# Main.net
KiCad netlist of a schematic drawn in Altium Designer
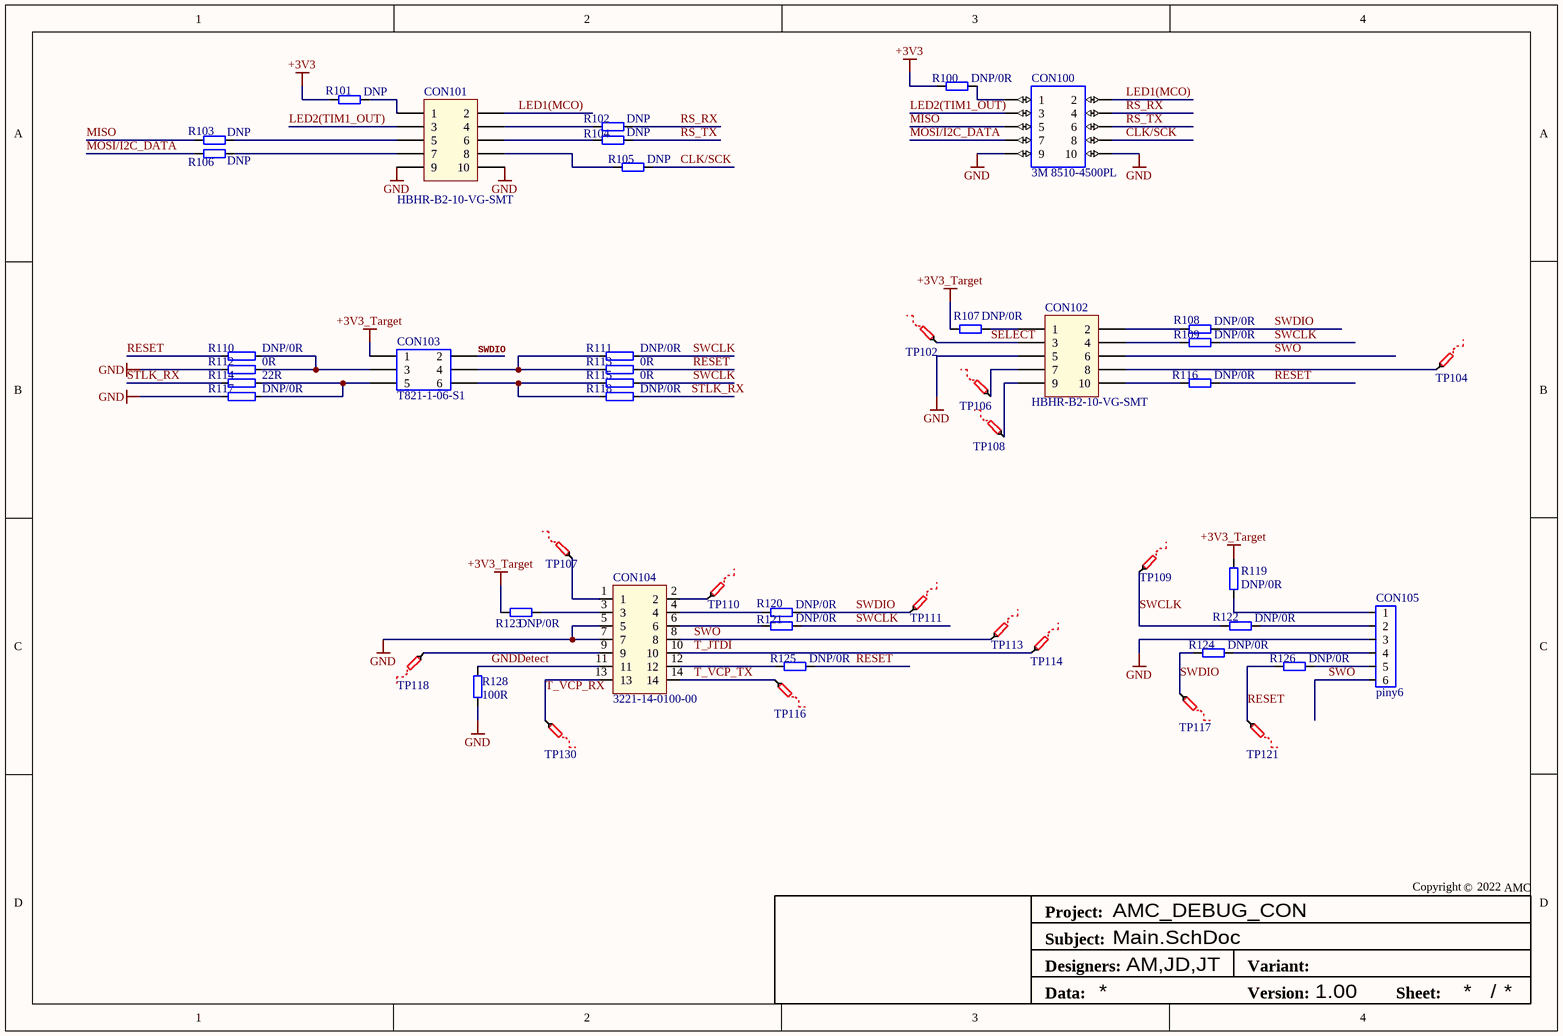
[diagram p0: Main.SchDoc]

(export (version "E")
  (design (tool "Eeschema 10.0.6"))
  (components
    (comp (ref "CON100")
      (value "3M 8510-4500PL")
      (footprint "PINY2X5 zenskie")
      (description "Gniazdo; IDC; żeńskie; PIN: 10; proste; THT; złocony; 3A; 2,54mm")
      (libsource (lib "ECS_AMC_all_2016") (part "piny_2x5 zenskie Petroster"))
    )
    (comp (ref "CON101")
      (value "HBHR-B2-10-VG-SMT")
      (footprint "piny_1k27_2x5_smd_IDC")
      (description "AMC Debug connector\r\nIDC 2x5 pitch 1.27")
      (libsource (lib "ECS_AMC_all_2016") (part "AMC_Debug"))
    )
    (comp (ref "CON102")
      (value "HBHR-B2-10-VG-SMT")
      (footprint "piny_1k27_2x5_smd_IDC")
      (description "AMC Debug connector\r\nIDC 2x5 pitch 1.27")
      (libsource (lib "ECS_AMC_all_2016") (part "AMC_Debug"))
    )
    (comp (ref "CON103")
      (value "T821-1-06-S1")
      (footprint "IDC_2X3_2.54MM")
      (libsource (lib "ECS_AMC_all_2016") (part "piny_2x3"))
    )
    (comp (ref "CON104")
      (value "3221-14-0100-00")
      (footprint "PINY_2X7_1.27_THT")
      (description "CONN HEADER VERT 14POS 1.27MM")
      (libsource (lib "ECS_AMC_all_2016") (part "3221-14-0100-00"))
    )
    (comp (ref "CON105")
      (value "piny6")
      (footprint "piny1x6")
      (libsource (lib "ECS_AMC_all_2016") (part "piny6"))
    )
    (comp (ref "R100") (value "DNP/0R") (footprint "0805") (libsource (lib "ECS_all_2014") (part "rez_3k")))
    (comp (ref "R101") (value "DNP") (footprint "0805") (libsource (lib "ECS_all_2014") (part "rez_3k")))
    (comp (ref "R102") (value "DNP") (footprint "0805") (libsource (lib "ECS_all_2014") (part "rez_3k")))
    (comp (ref "R103") (value "DNP") (footprint "0805") (libsource (lib "ECS_all_2014") (part "rez_3k")))
    (comp (ref "R104") (value "DNP") (footprint "0805") (libsource (lib "ECS_all_2014") (part "rez_3k")))
    (comp (ref "R105") (value "DNP") (footprint "0805") (libsource (lib "ECS_all_2014") (part "rez_3k")))
    (comp (ref "R106") (value "DNP") (footprint "0805") (libsource (lib "ECS_all_2014") (part "rez_3k")))
    (comp (ref "R107") (value "DNP/0R") (footprint "0805") (libsource (lib "ECS_all_2014") (part "rez_3k")))
    (comp (ref "R108") (value "DNP/0R") (footprint "0805") (libsource (lib "ECS_all_2014") (part "rez_3k")))
    (comp (ref "R109") (value "DNP/0R") (footprint "0805") (libsource (lib "ECS_all_2014") (part "rez_3k")))
    (comp (ref "R110") (value "DNP/0R") (footprint "0805") (libsource (lib "ECS_AMC_all_2016") (part "RES")))
    (comp (ref "R111") (value "DNP/0R") (footprint "0805") (libsource (lib "ECS_AMC_all_2016") (part "RES")))
    (comp (ref "R112") (value "0R") (footprint "0805") (libsource (lib "ECS_AMC_all_2016") (part "RES")))
    (comp (ref "R113") (value "0R") (footprint "0805") (libsource (lib "ECS_AMC_all_2016") (part "RES")))
    (comp (ref "R114") (value "22R") (footprint "0805") (libsource (lib "ECS_AMC_all_2016") (part "RES")))
    (comp (ref "R115") (value "0R") (footprint "0805") (libsource (lib "ECS_AMC_all_2016") (part "RES")))
    (comp (ref "R116") (value "DNP/0R") (footprint "0805") (libsource (lib "ECS_all_2014") (part "rez_3k")))
    (comp (ref "R117") (value "DNP/0R") (footprint "0805") (libsource (lib "ECS_AMC_all_2016") (part "RES")))
    (comp (ref "R118") (value "DNP/0R") (footprint "0805") (libsource (lib "ECS_AMC_all_2016") (part "RES")))
    (comp (ref "R119") (value "DNP/0R") (footprint "0805") (libsource (lib "") (part "rez_3k_1")))
    (comp (ref "R120") (value "DNP/0R") (footprint "0805") (libsource (lib "ECS_all_2014") (part "rez_3k")))
    (comp (ref "R121") (value "DNP/0R") (footprint "0805") (libsource (lib "ECS_all_2014") (part "rez_3k")))
    (comp (ref "R122") (value "DNP/0R") (footprint "0805") (libsource (lib "ECS_all_2014") (part "rez_3k")))
    (comp (ref "R123") (value "DNP/0R") (footprint "0805") (libsource (lib "") (part "rez_3k_2")))
    (comp (ref "R124") (value "DNP/0R") (footprint "0805") (libsource (lib "ECS_all_2014") (part "rez_3k")))
    (comp (ref "R125") (value "DNP/0R") (footprint "0805") (libsource (lib "ECS_all_2014") (part "rez_3k")))
    (comp (ref "R126") (value "DNP/0R") (footprint "0805") (libsource (lib "ECS_all_2014") (part "rez_3k")))
    (comp (ref "R128") (value "100R") (footprint "0805") (libsource (lib "") (part "rez_3k_1")))
    (comp (ref "TP102")
      (value "testpoint")
      (footprint "testpoint_50mils_octagonal")
      (description "Testpoint")
      (libsource (lib "ECS_AMC_all_2016") (part "testpoint"))
    )
    (comp (ref "TP104")
      (value "testpoint")
      (footprint "testpoint_50mils_octagonal")
      (description "Testpoint")
      (libsource (lib "ECS_AMC_all_2016") (part "testpoint"))
    )
    (comp (ref "TP106")
      (value "testpoint")
      (footprint "testpoint_50mils_octagonal")
      (description "Testpoint")
      (libsource (lib "ECS_AMC_all_2016") (part "testpoint"))
    )
    (comp (ref "TP107")
      (value "testpoint")
      (footprint "testpoint_50mils_octagonal")
      (description "Testpoint")
      (libsource (lib "ECS_AMC_all_2016") (part "testpoint"))
    )
    (comp (ref "TP108")
      (value "testpoint")
      (footprint "testpoint_50mils_octagonal")
      (description "Testpoint")
      (libsource (lib "ECS_AMC_all_2016") (part "testpoint"))
    )
    (comp (ref "TP109")
      (value "testpoint")
      (footprint "testpoint_50mils_octagonal")
      (description "Testpoint")
      (libsource (lib "ECS_AMC_all_2016") (part "testpoint"))
    )
    (comp (ref "TP110")
      (value "testpoint")
      (footprint "testpoint_50mils_octagonal")
      (description "Testpoint")
      (libsource (lib "ECS_AMC_all_2016") (part "testpoint"))
    )
    (comp (ref "TP111")
      (value "testpoint")
      (footprint "testpoint_50mils_octagonal")
      (description "Testpoint")
      (libsource (lib "ECS_AMC_all_2016") (part "testpoint"))
    )
    (comp (ref "TP113")
      (value "testpoint")
      (footprint "testpoint_50mils_octagonal")
      (description "Testpoint")
      (libsource (lib "ECS_AMC_all_2016") (part "testpoint"))
    )
    (comp (ref "TP114")
      (value "testpoint")
      (footprint "testpoint_50mils_octagonal")
      (description "Testpoint")
      (libsource (lib "ECS_AMC_all_2016") (part "testpoint"))
    )
    (comp (ref "TP116")
      (value "testpoint")
      (footprint "testpoint_50mils_octagonal")
      (description "Testpoint")
      (libsource (lib "ECS_AMC_all_2016") (part "testpoint"))
    )
    (comp (ref "TP117")
      (value "testpoint")
      (footprint "testpoint_50mils_octagonal")
      (description "Testpoint")
      (libsource (lib "ECS_AMC_all_2016") (part "testpoint"))
    )
    (comp (ref "TP118")
      (value "testpoint")
      (footprint "testpoint_50mils_octagonal")
      (description "Testpoint")
      (libsource (lib "ECS_AMC_all_2016") (part "testpoint"))
    )
    (comp (ref "TP121")
      (value "testpoint")
      (footprint "testpoint_50mils_octagonal")
      (description "Testpoint")
      (libsource (lib "ECS_AMC_all_2016") (part "testpoint"))
    )
    (comp (ref "TP130")
      (value "testpoint")
      (footprint "testpoint_50mils_octagonal")
      (description "Testpoint")
      (libsource (lib "ECS_AMC_all_2016") (part "testpoint"))
    )
  )
  (nets
    (net (code "1") (name "+3V3") (class "Default")
      (node (ref "R100") (pin "1") (pinfunction "1_1") (pintype "passive"))
      (node (ref "R101") (pin "1") (pinfunction "1_1") (pintype "passive"))
    )
    (net (code "2") (name "+3V3_Target") (class "Default")
      (node (ref "CON103") (pin "1") (pinfunction "1_1") (pintype "passive"))
      (node (ref "R107") (pin "1") (pinfunction "1_1") (pintype "passive"))
      (node (ref "R119") (pin "2") (pinfunction "2_2") (pintype "passive"))
      (node (ref "R123") (pin "2") (pinfunction "2_2") (pintype "passive"))
    )
    (net (code "3") (name "/CLK{slash}SCK") (class "Default")
      (node (ref "CON100") (pin "8") (pinfunction "8_8") (pintype "bidirectional"))
      (node (ref "R105") (pin "2") (pinfunction "2_2") (pintype "passive"))
    )
    (net (code "4") (name "/GNDDetect") (class "Default")
      (node (ref "CON104") (pin "11") (pinfunction "11_11") (pintype "passive"))
      (node (ref "R128") (pin "2") (pinfunction "2_2") (pintype "passive"))
    )
    (net (code "5") (name "/LED1(MCO)") (class "Default")
      (node (ref "CON100") (pin "2") (pinfunction "2_2") (pintype "bidirectional"))
      (node (ref "CON101") (pin "2") (pinfunction "2_2") (pintype "passive"))
    )
    (net (code "6") (name "/LED2(TIM1_OUT)") (class "Default")
      (node (ref "CON100") (pin "3") (pinfunction "3_3") (pintype "bidirectional"))
      (node (ref "CON101") (pin "3") (pinfunction "3_3") (pintype "passive"))
    )
    (net (code "7") (name "/MISO") (class "Default")
      (node (ref "CON100") (pin "5") (pinfunction "5_5") (pintype "bidirectional"))
      (node (ref "R103") (pin "1") (pinfunction "1_1") (pintype "passive"))
    )
    (net (code "8") (name "/MOSI{slash}I2C_DATA") (class "Default")
      (node (ref "CON100") (pin "7") (pinfunction "7_7") (pintype "bidirectional"))
      (node (ref "R106") (pin "1") (pinfunction "1_1") (pintype "passive"))
    )
    (net (code "9") (name "/RESET") (class "Default")
      (node (ref "R110") (pin "2") (pinfunction "2_2") (pintype "passive"))
      (node (ref "R113") (pin "1") (pinfunction "1_1") (pintype "passive"))
      (node (ref "R116") (pin "2") (pinfunction "2_2") (pintype "passive"))
      (node (ref "R125") (pin "2") (pinfunction "2_2") (pintype "passive"))
      (node (ref "R126") (pin "1") (pinfunction "1_1") (pintype "passive"))
      (node (ref "TP121") (pin "1") (pinfunction "1_1") (pintype "passive"))
    )
    (net (code "10") (name "/RS_RX") (class "Default")
      (node (ref "CON100") (pin "4") (pinfunction "4_4") (pintype "bidirectional"))
      (node (ref "R102") (pin "2") (pinfunction "2_2") (pintype "passive"))
    )
    (net (code "11") (name "/RS_TX") (class "Default")
      (node (ref "CON100") (pin "6") (pinfunction "6_6") (pintype "bidirectional"))
      (node (ref "R104") (pin "2") (pinfunction "2_2") (pintype "passive"))
    )
    (net (code "12") (name "/SELECT") (class "Default")
      (node (ref "CON102") (pin "3") (pinfunction "3_3") (pintype "passive"))
      (node (ref "TP102") (pin "1") (pinfunction "1_1") (pintype "passive"))
    )
    (net (code "13") (name "/STLK_RX") (class "Default")
      (node (ref "R114") (pin "2") (pinfunction "2_2") (pintype "passive"))
      (node (ref "R118") (pin "1") (pinfunction "1_1") (pintype "passive"))
    )
    (net (code "14") (name "/SWCLK") (class "Default")
      (node (ref "R109") (pin "2") (pinfunction "2_2") (pintype "passive"))
      (node (ref "R111") (pin "1") (pinfunction "1_1") (pintype "passive"))
      (node (ref "R115") (pin "1") (pinfunction "1_1") (pintype "passive"))
      (node (ref "R121") (pin "2") (pinfunction "2_2") (pintype "passive"))
      (node (ref "R122") (pin "1") (pinfunction "1_1") (pintype "passive"))
      (node (ref "TP109") (pin "1") (pinfunction "1_1") (pintype "passive"))
    )
    (net (code "15") (name "/SWDIO") (class "Default")
      (node (ref "CON103") (pin "2") (pinfunction "2_2") (pintype "passive"))
      (node (ref "R108") (pin "2") (pinfunction "2_2") (pintype "passive"))
      (node (ref "R120") (pin "2") (pinfunction "2_2") (pintype "passive"))
      (node (ref "R124") (pin "1") (pinfunction "1_1") (pintype "passive"))
      (node (ref "TP111") (pin "1") (pinfunction "1_1") (pintype "passive"))
      (node (ref "TP117") (pin "1") (pinfunction "1_1") (pintype "passive"))
    )
    (net (code "16") (name "/SWO") (class "Default")
      (node (ref "CON102") (pin "6") (pinfunction "6_6") (pintype "passive"))
      (node (ref "CON104") (pin "8") (pinfunction "8_8") (pintype "passive"))
      (node (ref "CON105") (pin "6") (pinfunction "6_6") (pintype "passive"))
      (node (ref "TP113") (pin "1") (pinfunction "1_1") (pintype "passive"))
    )
    (net (code "17") (name "/T_JTDI") (class "Default")
      (node (ref "CON104") (pin "10") (pinfunction "10_10") (pintype "passive"))
      (node (ref "TP114") (pin "1") (pinfunction "1_1") (pintype "passive"))
    )
    (net (code "18") (name "/T_VCP_RX") (class "Default")
      (node (ref "CON104") (pin "13") (pinfunction "13_13") (pintype "passive"))
      (node (ref "TP130") (pin "1") (pinfunction "1_1") (pintype "passive"))
    )
    (net (code "19") (name "/T_VCP_TX") (class "Default")
      (node (ref "CON104") (pin "14") (pinfunction "14_14") (pintype "passive"))
      (node (ref "TP116") (pin "1") (pinfunction "1_1") (pintype "passive"))
    )
    (net (code "20") (name "GND") (class "Default")
      (node (ref "CON100") (pin "10") (pinfunction "10_10") (pintype "bidirectional"))
      (node (ref "CON100") (pin "9") (pinfunction "9_9") (pintype "bidirectional"))
      (node (ref "CON101") (pin "10") (pinfunction "10_10") (pintype "passive"))
      (node (ref "CON101") (pin "9") (pinfunction "9_9") (pintype "passive"))
      (node (ref "CON102") (pin "5") (pinfunction "5_5") (pintype "passive"))
      (node (ref "CON104") (pin "5") (pinfunction "5_5") (pintype "passive"))
      (node (ref "CON104") (pin "7") (pinfunction "7_7") (pintype "passive"))
      (node (ref "CON105") (pin "3") (pinfunction "3_3") (pintype "passive"))
      (node (ref "R112") (pin "2") (pinfunction "2_2") (pintype "passive"))
      (node (ref "R117") (pin "2") (pinfunction "2_2") (pintype "passive"))
      (node (ref "R128") (pin "1") (pinfunction "1_1") (pintype "passive"))
    )
    (net (code "21") (name "Net-(CON100-Pad1)") (class "Default")
      (node (ref "CON100") (pin "1") (pinfunction "1_1") (pintype "bidirectional"))
      (node (ref "R100") (pin "2") (pinfunction "2_2") (pintype "passive"))
    )
    (net (code "22") (name "Net-(CON101-Pad1)") (class "Default")
      (node (ref "CON101") (pin "1") (pinfunction "1_1") (pintype "passive"))
      (node (ref "R101") (pin "2") (pinfunction "2_2") (pintype "passive"))
    )
    (net (code "23") (name "Net-(CON101-Pad4)") (class "Default")
      (node (ref "CON101") (pin "4") (pinfunction "4_4") (pintype "passive"))
      (node (ref "R102") (pin "1") (pinfunction "1_1") (pintype "passive"))
    )
    (net (code "24") (name "Net-(CON101-Pad5)") (class "Default")
      (node (ref "CON101") (pin "5") (pinfunction "5_5") (pintype "passive"))
      (node (ref "R103") (pin "2") (pinfunction "2_2") (pintype "passive"))
    )
    (net (code "25") (name "Net-(CON101-Pad6)") (class "Default")
      (node (ref "CON101") (pin "6") (pinfunction "6_6") (pintype "passive"))
      (node (ref "R104") (pin "1") (pinfunction "1_1") (pintype "passive"))
    )
    (net (code "26") (name "Net-(CON101-Pad7)") (class "Default")
      (node (ref "CON101") (pin "7") (pinfunction "7_7") (pintype "passive"))
      (node (ref "R106") (pin "2") (pinfunction "2_2") (pintype "passive"))
    )
    (net (code "27") (name "Net-(CON101-Pad8)") (class "Default")
      (node (ref "CON101") (pin "8") (pinfunction "8_8") (pintype "passive"))
      (node (ref "R105") (pin "1") (pinfunction "1_1") (pintype "passive"))
    )
    (net (code "28") (name "Net-(CON102-Pad1)") (class "Default")
      (node (ref "CON102") (pin "1") (pinfunction "1_1") (pintype "passive"))
      (node (ref "R107") (pin "2") (pinfunction "2_2") (pintype "passive"))
    )
    (net (code "29") (name "Net-(CON102-Pad2)") (class "Default")
      (node (ref "CON102") (pin "2") (pinfunction "2_2") (pintype "passive"))
      (node (ref "R108") (pin "1") (pinfunction "1_1") (pintype "passive"))
    )
    (net (code "30") (name "Net-(CON102-Pad4)") (class "Default")
      (node (ref "CON102") (pin "4") (pinfunction "4_4") (pintype "passive"))
      (node (ref "R109") (pin "1") (pinfunction "1_1") (pintype "passive"))
    )
    (net (code "31") (name "Net-(CON102-Pad7)") (class "Default")
      (node (ref "CON102") (pin "7") (pinfunction "7_7") (pintype "passive"))
      (node (ref "TP106") (pin "1") (pinfunction "1_1") (pintype "passive"))
    )
    (net (code "32") (name "Net-(CON102-Pad8)") (class "Default")
      (node (ref "CON102") (pin "8") (pinfunction "8_8") (pintype "passive"))
      (node (ref "TP104") (pin "1") (pinfunction "1_1") (pintype "passive"))
    )
    (net (code "33") (name "Net-(CON102-Pad9)") (class "Default")
      (node (ref "CON102") (pin "9") (pinfunction "9_9") (pintype "passive"))
      (node (ref "TP108") (pin "1") (pinfunction "1_1") (pintype "passive"))
    )
    (net (code "34") (name "Net-(CON102-Pad10)") (class "Default")
      (node (ref "CON102") (pin "10") (pinfunction "10_10") (pintype "passive"))
      (node (ref "R116") (pin "1") (pinfunction "1_1") (pintype "passive"))
    )
    (net (code "35") (name "Net-(CON103-Pad3)") (class "Default")
      (node (ref "CON103") (pin "3") (pinfunction "3_3") (pintype "passive"))
      (node (ref "R110") (pin "1") (pinfunction "1_1") (pintype "passive"))
      (node (ref "R112") (pin "1") (pinfunction "1_1") (pintype "passive"))
    )
    (net (code "36") (name "Net-(CON103-Pad4)") (class "Default")
      (node (ref "CON103") (pin "4") (pinfunction "4_4") (pintype "passive"))
      (node (ref "R111") (pin "2") (pinfunction "2_2") (pintype "passive"))
      (node (ref "R113") (pin "2") (pinfunction "2_2") (pintype "passive"))
    )
    (net (code "37") (name "Net-(CON103-Pad5)") (class "Default")
      (node (ref "CON103") (pin "5") (pinfunction "5_5") (pintype "passive"))
      (node (ref "R114") (pin "1") (pinfunction "1_1") (pintype "passive"))
      (node (ref "R117") (pin "1") (pinfunction "1_1") (pintype "passive"))
    )
    (net (code "38") (name "Net-(CON103-Pad6)") (class "Default")
      (node (ref "CON103") (pin "6") (pinfunction "6_6") (pintype "passive"))
      (node (ref "R115") (pin "2") (pinfunction "2_2") (pintype "passive"))
      (node (ref "R118") (pin "2") (pinfunction "2_2") (pintype "passive"))
    )
    (net (code "39") (name "Net-(CON104-Pad1)") (class "Default")
      (node (ref "CON104") (pin "1") (pinfunction "1_1") (pintype "passive"))
      (node (ref "TP107") (pin "1") (pinfunction "1_1") (pintype "passive"))
    )
    (net (code "40") (name "Net-(CON104-Pad2)") (class "Default")
      (node (ref "CON104") (pin "2") (pinfunction "2_2") (pintype "passive"))
      (node (ref "TP110") (pin "1") (pinfunction "1_1") (pintype "passive"))
    )
    (net (code "41") (name "Net-(CON104-Pad3)") (class "Default")
      (node (ref "CON104") (pin "3") (pinfunction "3_3") (pintype "passive"))
      (node (ref "R123") (pin "1") (pinfunction "1_1") (pintype "passive"))
    )
    (net (code "42") (name "Net-(CON104-Pad4)") (class "Default")
      (node (ref "CON104") (pin "4") (pinfunction "4_4") (pintype "passive"))
      (node (ref "R120") (pin "1") (pinfunction "1_1") (pintype "passive"))
    )
    (net (code "43") (name "Net-(CON104-Pad6)") (class "Default")
      (node (ref "CON104") (pin "6") (pinfunction "6_6") (pintype "passive"))
      (node (ref "R121") (pin "1") (pinfunction "1_1") (pintype "passive"))
    )
    (net (code "44") (name "Net-(CON104-Pad9)") (class "Default")
      (node (ref "CON104") (pin "9") (pinfunction "9_9") (pintype "passive"))
      (node (ref "TP118") (pin "1") (pinfunction "1_1") (pintype "passive"))
    )
    (net (code "45") (name "Net-(CON104-Pad12)") (class "Default")
      (node (ref "CON104") (pin "12") (pinfunction "12_12") (pintype "passive"))
      (node (ref "R125") (pin "1") (pinfunction "1_1") (pintype "passive"))
    )
    (net (code "46") (name "Net-(CON105-Pad1)") (class "Default")
      (node (ref "CON105") (pin "1") (pinfunction "1_1") (pintype "passive"))
      (node (ref "R119") (pin "1") (pinfunction "1_1") (pintype "passive"))
    )
    (net (code "47") (name "Net-(CON105-Pad2)") (class "Default")
      (node (ref "CON105") (pin "2") (pinfunction "2_2") (pintype "passive"))
      (node (ref "R122") (pin "2") (pinfunction "2_2") (pintype "passive"))
    )
    (net (code "48") (name "Net-(CON105-Pad4)") (class "Default")
      (node (ref "CON105") (pin "4") (pinfunction "4_4") (pintype "passive"))
      (node (ref "R124") (pin "2") (pinfunction "2_2") (pintype "passive"))
    )
    (net (code "49") (name "Net-(CON105-Pad5)") (class "Default")
      (node (ref "CON105") (pin "5") (pinfunction "5_5") (pintype "passive"))
      (node (ref "R126") (pin "2") (pinfunction "2_2") (pintype "passive"))
    )
  )
)
